# EuroESP32.net
KiCad netlist of a schematic drawn in EAGLE
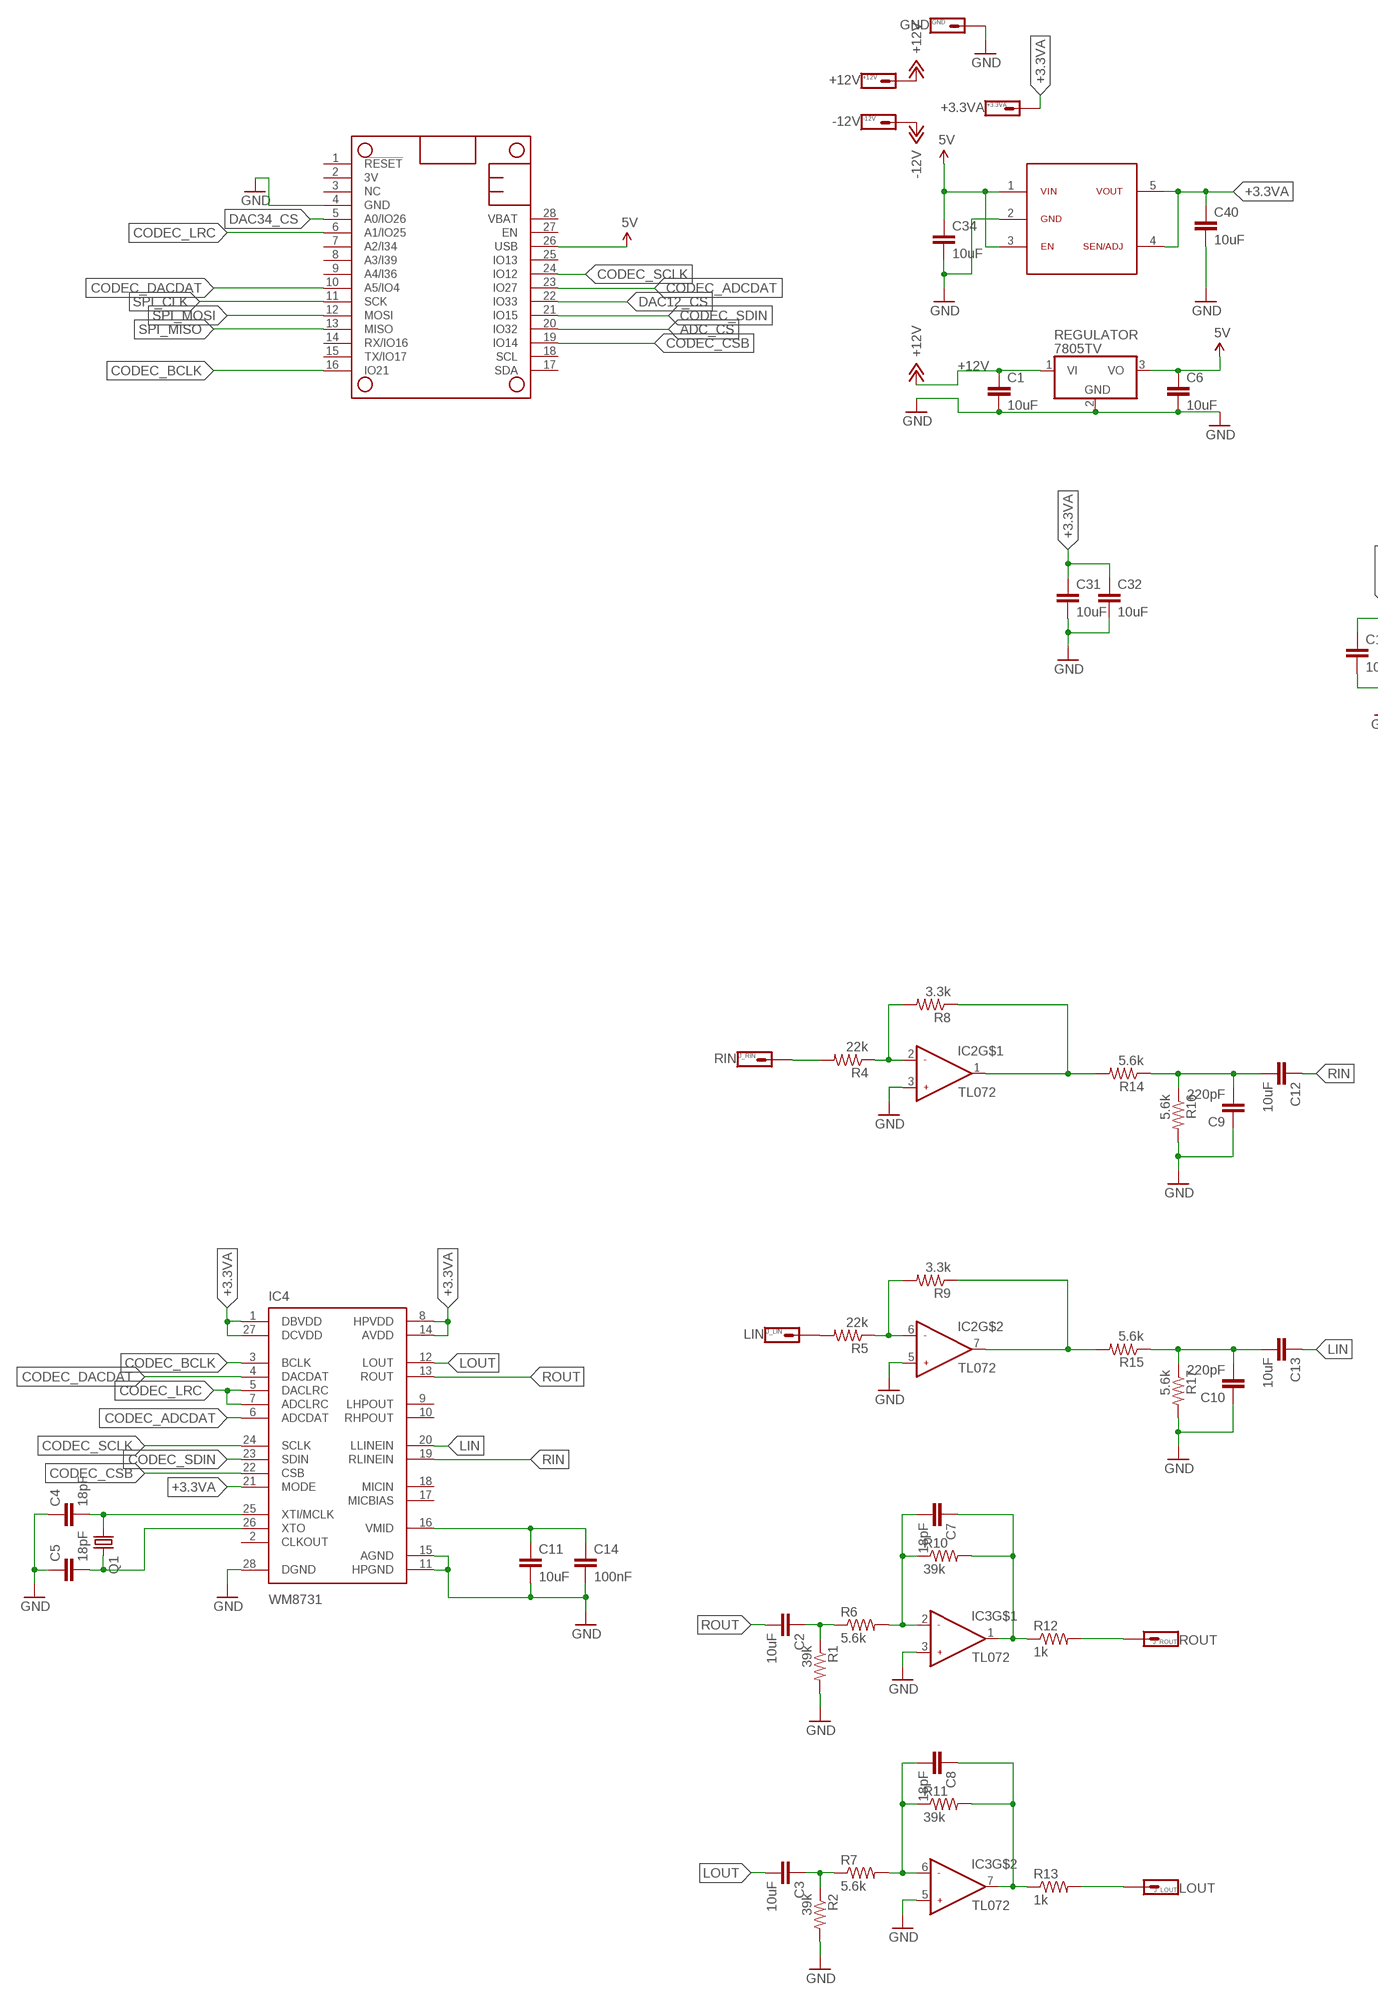
[diagram p0: schematic, sheet 1, part 1 of 2]
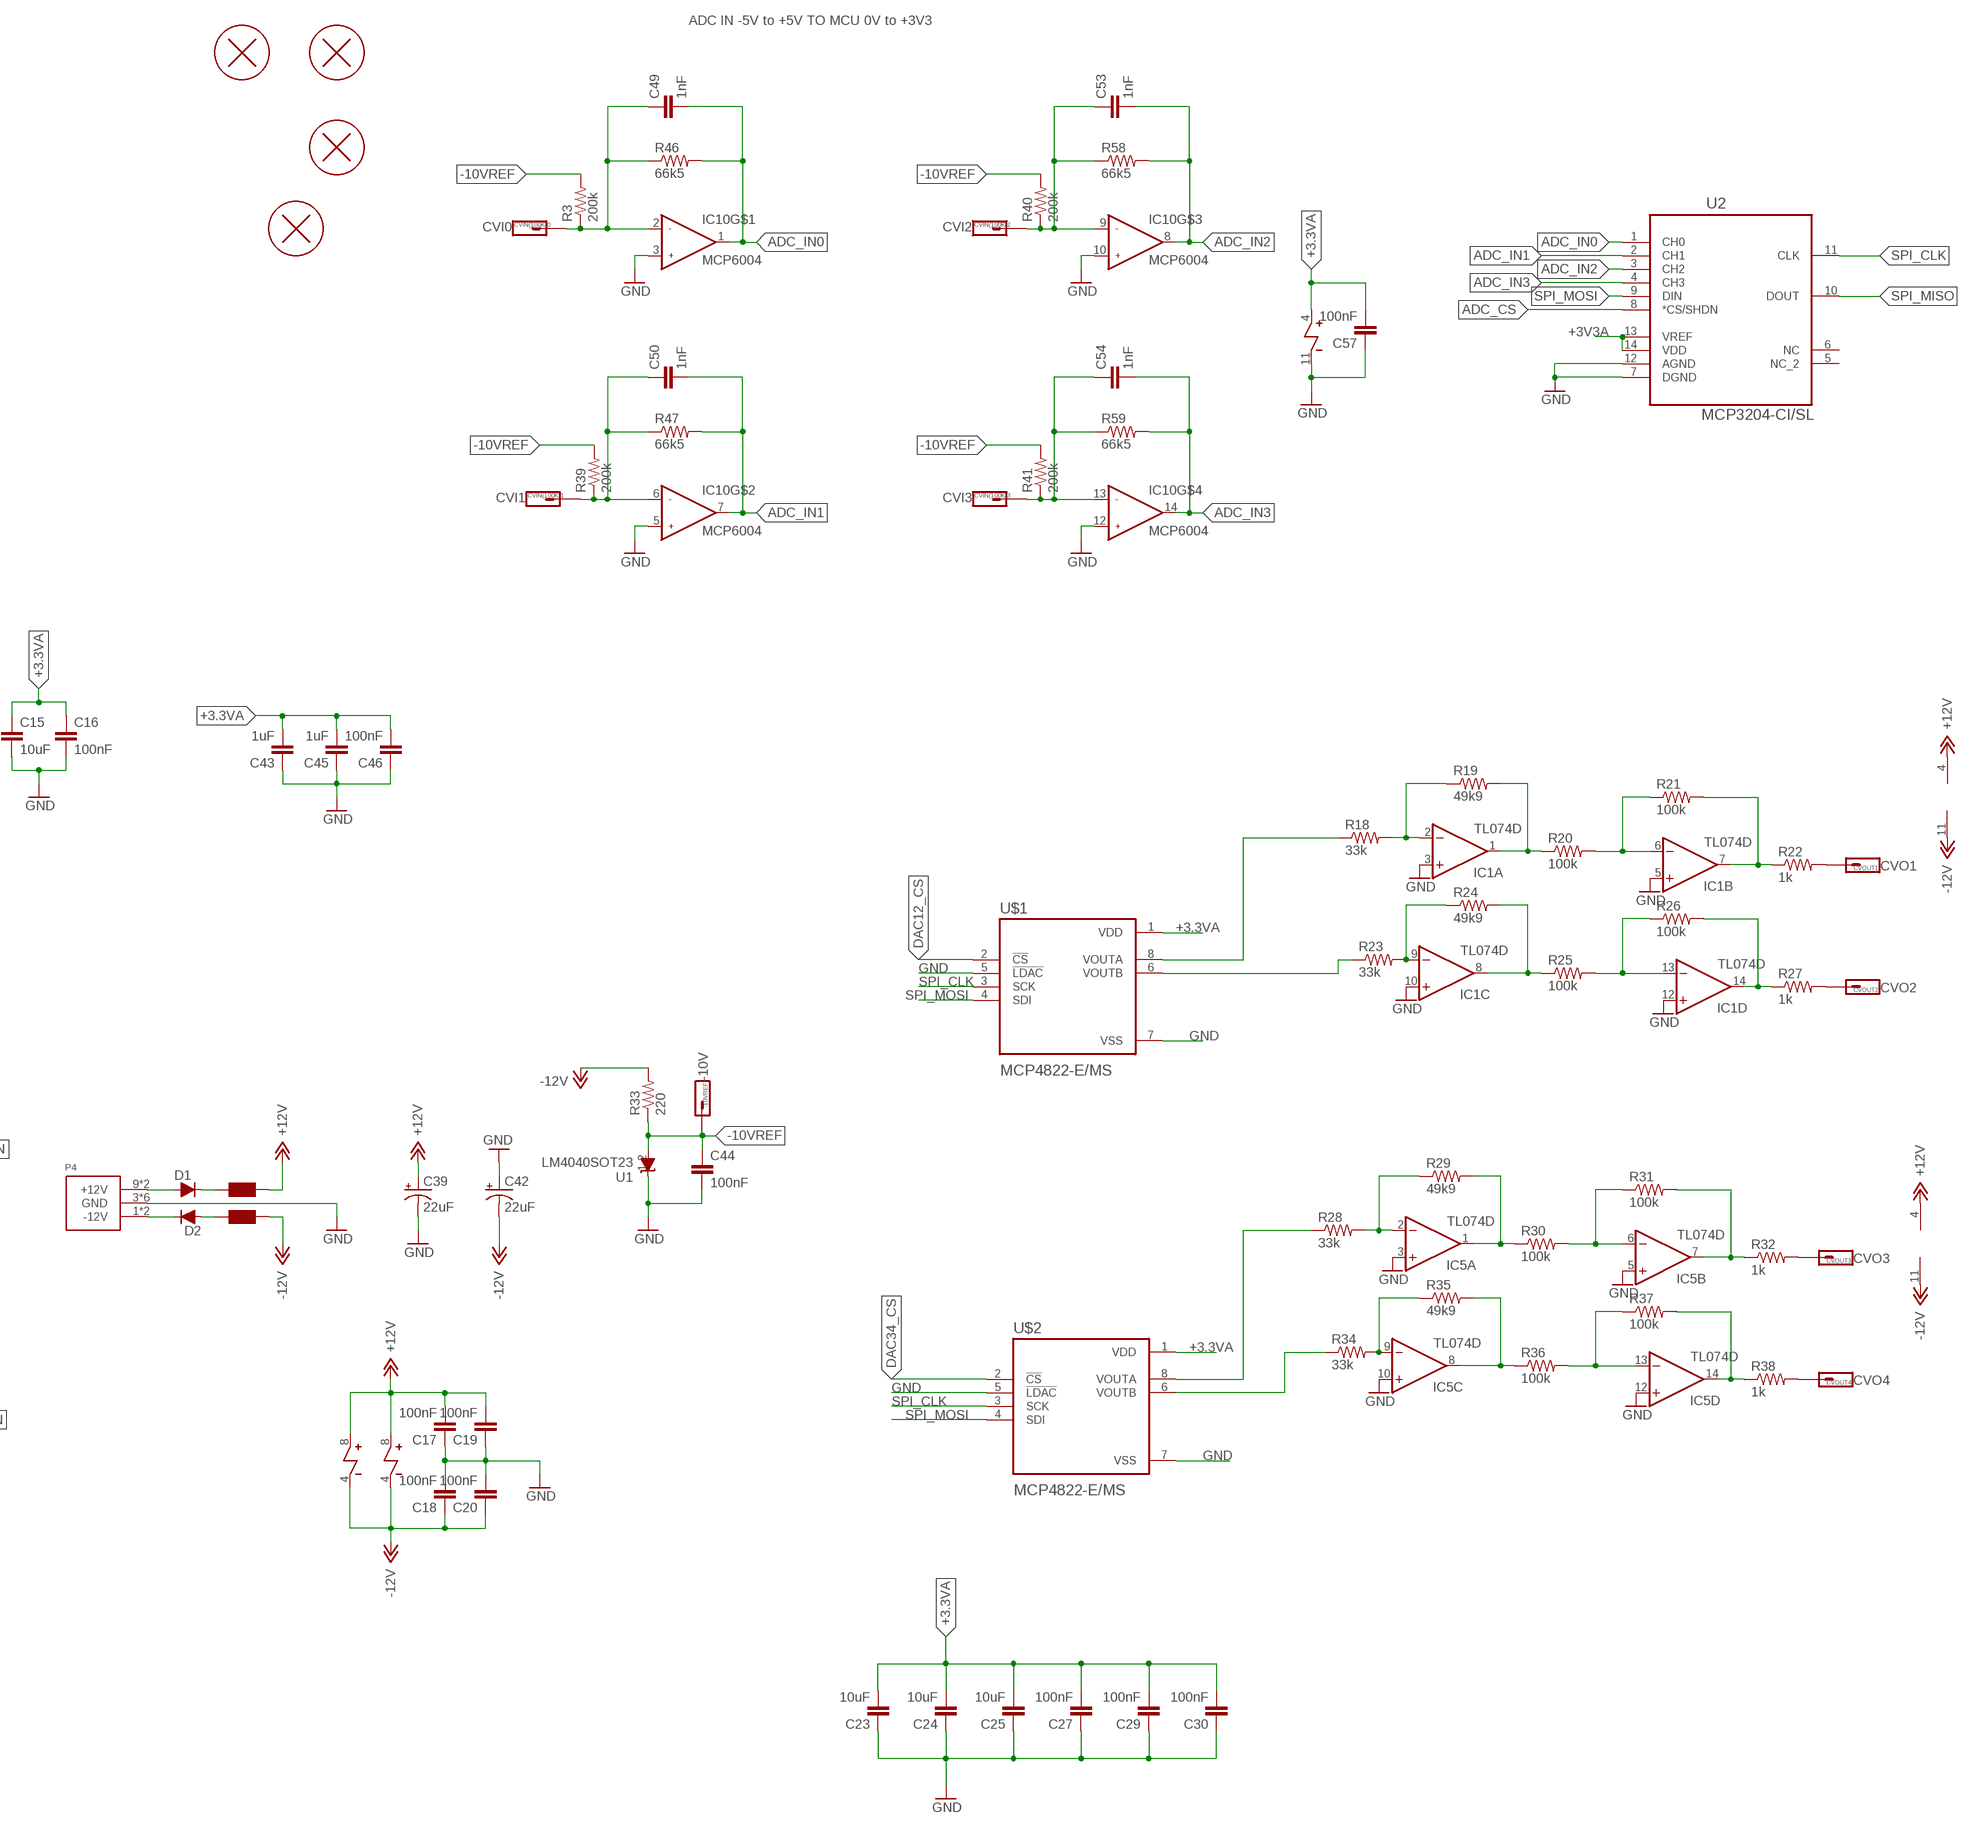
[diagram p1: schematic, sheet 1, part 2 of 2]

(export (version "E")
  (design (tool "Eeschema 10.0.6"))
  (components
    (comp (ref "+3.3VA")
      (value "+3.3VA")
      (footprint "eagle-import:1X01_SIDE_NAME")
      (libsource (lib "eagle-import") (part "HEADER-1X1"))
    )
    (comp (ref "+12V")
      (value "+12V")
      (footprint "eagle-import:1X01_SIDE_NAME")
      (libsource (lib "eagle-import") (part "HEADER-1X1"))
    )
    (comp (ref "-10VREF")
      (value "-10V")
      (footprint "eagle-import:1X01_SIDE_NAME")
      (libsource (lib "eagle-import") (part "HEADER-1X1"))
    )
    (comp (ref "-12V")
      (value "-12V")
      (footprint "eagle-import:1X01_SIDE_NAME")
      (libsource (lib "eagle-import") (part "HEADER-1X1"))
    )
    (comp (ref "C1")
      (value "10uF")
      (footprint "eagle-import:C2.5-2")
      (libsource (lib "eagle-import") (part "C2.5/2"))
    )
    (comp (ref "C2")
      (value "10uF")
      (footprint "eagle-import:R0805")
      (libsource (lib "eagle-import") (part "CAPACITOR0805"))
    )
    (comp (ref "C3")
      (value "10uF")
      (footprint "eagle-import:R0805")
      (libsource (lib "eagle-import") (part "CAPACITOR0805"))
    )
    (comp (ref "C4")
      (value "18pF")
      (footprint "eagle-import:RESISTOR_0603")
      (libsource (lib "eagle-import") (part "CAPACITOR"))
    )
    (comp (ref "C5")
      (value "18pF")
      (footprint "eagle-import:RESISTOR_0603")
      (libsource (lib "eagle-import") (part "CAPACITOR"))
    )
    (comp (ref "C6")
      (value "10uF")
      (footprint "eagle-import:C2.5-2")
      (libsource (lib "eagle-import") (part "C2.5/2"))
    )
    (comp (ref "C7")
      (value "18pF")
      (footprint "eagle-import:RESISTOR_0603")
      (libsource (lib "eagle-import") (part "CAPACITOR"))
    )
    (comp (ref "C8")
      (value "18pF")
      (footprint "eagle-import:RESISTOR_0603")
      (libsource (lib "eagle-import") (part "CAPACITOR"))
    )
    (comp (ref "C9")
      (value "220pF")
      (footprint "eagle-import:RESISTOR_0603")
      (libsource (lib "eagle-import") (part "CAPACITOR"))
    )
    (comp (ref "C10")
      (value "220pF")
      (footprint "eagle-import:RESISTOR_0603")
      (libsource (lib "eagle-import") (part "CAPACITOR"))
    )
    (comp (ref "C11")
      (value "10uF")
      (footprint "eagle-import:R0805")
      (libsource (lib "eagle-import") (part "CAPACITOR0805"))
    )
    (comp (ref "C12")
      (value "10uF")
      (footprint "eagle-import:R0805")
      (libsource (lib "eagle-import") (part "CAPACITOR0805"))
    )
    (comp (ref "C13")
      (value "10uF")
      (footprint "eagle-import:R0805")
      (libsource (lib "eagle-import") (part "CAPACITOR0805"))
    )
    (comp (ref "C14")
      (value "100nF")
      (footprint "eagle-import:RESISTOR_0603")
      (libsource (lib "eagle-import") (part "CAPACITOR"))
    )
    (comp (ref "C15")
      (value "10uF")
      (footprint "eagle-import:R0805")
      (libsource (lib "eagle-import") (part "CAPACITOR0805"))
    )
    (comp (ref "C16")
      (value "100nF")
      (footprint "eagle-import:RESISTOR_0603")
      (libsource (lib "eagle-import") (part "CAPACITOR"))
    )
    (comp (ref "C17")
      (value "100nF")
      (footprint "eagle-import:RESISTOR_0603")
      (libsource (lib "eagle-import") (part "CAPACITOR"))
    )
    (comp (ref "C18")
      (value "100nF")
      (footprint "eagle-import:RESISTOR_0603")
      (libsource (lib "eagle-import") (part "CAPACITOR"))
    )
    (comp (ref "C19")
      (value "100nF")
      (footprint "eagle-import:RESISTOR_0603")
      (libsource (lib "eagle-import") (part "CAPACITOR"))
    )
    (comp (ref "C20")
      (value "100nF")
      (footprint "eagle-import:RESISTOR_0603")
      (libsource (lib "eagle-import") (part "CAPACITOR"))
    )
    (comp (ref "C23")
      (value "10uF")
      (footprint "eagle-import:R0805")
      (libsource (lib "eagle-import") (part "CAPACITOR0805"))
    )
    (comp (ref "C24")
      (value "10uF")
      (footprint "eagle-import:R0805")
      (libsource (lib "eagle-import") (part "CAPACITOR0805"))
    )
    (comp (ref "C25")
      (value "10uF")
      (footprint "eagle-import:R0805")
      (libsource (lib "eagle-import") (part "CAPACITOR0805"))
    )
    (comp (ref "C27")
      (value "100nF")
      (footprint "eagle-import:RESISTOR_0603")
      (libsource (lib "eagle-import") (part "CAPACITOR"))
    )
    (comp (ref "C29")
      (value "100nF")
      (footprint "eagle-import:RESISTOR_0603")
      (libsource (lib "eagle-import") (part "CAPACITOR"))
    )
    (comp (ref "C30")
      (value "100nF")
      (footprint "eagle-import:RESISTOR_0603")
      (libsource (lib "eagle-import") (part "CAPACITOR"))
    )
    (comp (ref "C31")
      (value "10uF")
      (footprint "eagle-import:R0805")
      (libsource (lib "eagle-import") (part "CAPACITOR0805"))
    )
    (comp (ref "C32")
      (value "10uF")
      (footprint "eagle-import:R0805")
      (libsource (lib "eagle-import") (part "CAPACITOR0805"))
    )
    (comp (ref "C34")
      (value "10uF")
      (footprint "eagle-import:R1210")
      (libsource (lib "eagle-import") (part "CAPACITOR1210"))
    )
    (comp (ref "C39")
      (value "22uF")
      (footprint "eagle-import:1206_POL")
      (libsource (lib "eagle-import") (part "CAP_POL1206_TANT"))
    )
    (comp (ref "C40")
      (value "10uF")
      (footprint "eagle-import:R0805")
      (libsource (lib "eagle-import") (part "CAPACITOR0805"))
    )
    (comp (ref "C42")
      (value "22uF")
      (footprint "eagle-import:1206_POL")
      (libsource (lib "eagle-import") (part "CAP_POL1206_TANT"))
    )
    (comp (ref "C43")
      (value "1uF")
      (footprint "eagle-import:RESISTOR_0603")
      (libsource (lib "eagle-import") (part "CAPACITOR"))
    )
    (comp (ref "C44")
      (value "100nF")
      (footprint "eagle-import:RESISTOR_0603")
      (libsource (lib "eagle-import") (part "CAPACITOR"))
    )
    (comp (ref "C45")
      (value "1uF")
      (footprint "eagle-import:RESISTOR_0603")
      (libsource (lib "eagle-import") (part "CAPACITOR"))
    )
    (comp (ref "C46")
      (value "100nF")
      (footprint "eagle-import:RESISTOR_0603")
      (libsource (lib "eagle-import") (part "CAPACITOR"))
    )
    (comp (ref "C49")
      (value "1nF")
      (footprint "eagle-import:RESISTOR_0603")
      (libsource (lib "eagle-import") (part "CAPACITOR"))
    )
    (comp (ref "C50")
      (value "1nF")
      (footprint "eagle-import:RESISTOR_0603")
      (libsource (lib "eagle-import") (part "CAPACITOR"))
    )
    (comp (ref "C53")
      (value "1nF")
      (footprint "eagle-import:RESISTOR_0603")
      (libsource (lib "eagle-import") (part "CAPACITOR"))
    )
    (comp (ref "C54")
      (value "1nF")
      (footprint "eagle-import:RESISTOR_0603")
      (libsource (lib "eagle-import") (part "CAPACITOR"))
    )
    (comp (ref "C57")
      (value "100nF")
      (footprint "eagle-import:RESISTOR_0603")
      (libsource (lib "eagle-import") (part "CAPACITOR"))
    )
    (comp (ref "CVIN(100K)0")
      (value "CVI0")
      (footprint "eagle-import:1X01_SIDE_NAME")
      (libsource (lib "eagle-import") (part "HEADER-1X1"))
    )
    (comp (ref "CVIN(100K)1")
      (value "CVI1")
      (footprint "eagle-import:1X01_SIDE_NAME")
      (libsource (lib "eagle-import") (part "HEADER-1X1"))
    )
    (comp (ref "CVIN(100K)2")
      (value "CVI2")
      (footprint "eagle-import:1X01_SIDE_NAME")
      (libsource (lib "eagle-import") (part "HEADER-1X1"))
    )
    (comp (ref "CVIN(100K)3")
      (value "CVI3")
      (footprint "eagle-import:1X01_SIDE_NAME")
      (libsource (lib "eagle-import") (part "HEADER-1X1"))
    )
    (comp (ref "CVOUT1")
      (value "CVO1")
      (footprint "eagle-import:1X01_SIDE_NAME")
      (libsource (lib "eagle-import") (part "HEADER-1X1"))
    )
    (comp (ref "CVOUT2")
      (value "CVO2")
      (footprint "eagle-import:1X01_SIDE_NAME")
      (libsource (lib "eagle-import") (part "HEADER-1X1"))
    )
    (comp (ref "CVOUT3")
      (value "CVO3")
      (footprint "eagle-import:1X01_SIDE_NAME")
      (libsource (lib "eagle-import") (part "HEADER-1X1"))
    )
    (comp (ref "CVOUT4")
      (value "CVO4")
      (footprint "eagle-import:1X01_SIDE_NAME")
      (libsource (lib "eagle-import") (part "HEADER-1X1"))
    )
    (comp (ref "D1")
      (value "DIODE")
      (footprint "eagle-import:SOD123")
      (libsource (lib "eagle-import") (part "DIODE"))
    )
    (comp (ref "D2")
      (value "DIODE")
      (footprint "eagle-import:SOD123")
      (libsource (lib "eagle-import") (part "DIODE"))
    )
    (comp (ref "F1")
      (value "FERRITE-BEAD0805")
      (footprint "eagle-import:R0805")
      (libsource (lib "eagle-import") (part "FERRITE-BEAD0805"))
    )
    (comp (ref "F2")
      (value "FERRITE-BEAD0805")
      (footprint "eagle-import:R0805")
      (libsource (lib "eagle-import") (part "FERRITE-BEAD0805"))
    )
    (comp (ref "GND")
      (value "GND")
      (footprint "eagle-import:1X01_SIDE_NAME")
      (libsource (lib "eagle-import") (part "HEADER-1X1"))
    )
    (comp (ref "H1")
      (value "PCB_SCREW")
      (footprint "eagle-import:PCB_SCREW")
      (libsource (lib "eagle-import") (part "PCB_SCREW"))
    )
    (comp (ref "H3")
      (value "PCB_SCREW")
      (footprint "eagle-import:PCB_SCREW")
      (libsource (lib "eagle-import") (part "PCB_SCREW"))
    )
    (comp (ref "H4")
      (value "PCB_SCREW")
      (footprint "eagle-import:PCB_SCREW")
      (libsource (lib "eagle-import") (part "PCB_SCREW"))
    )
    (comp (ref "H5")
      (value "PCB_SCREW")
      (footprint "eagle-import:PCB_SCREW")
      (libsource (lib "eagle-import") (part "PCB_SCREW"))
    )
    (comp (ref "IC1")
      (value "TL074D")
      (footprint "eagle-import:SO14")
      (libsource (lib "eagle-import") (part "TL074D"))
    )
    (comp (ref "IC2")
      (value "TL072")
      (footprint "eagle-import:SOIC8")
      (libsource (lib "eagle-import") (part "OPAMP_DUAL"))
    )
    (comp (ref "IC3")
      (value "TL072")
      (footprint "eagle-import:SOIC8")
      (libsource (lib "eagle-import") (part "OPAMP_DUAL"))
    )
    (comp (ref "IC4")
      (value "WM8731")
      (footprint "eagle-import:SSOP28")
      (libsource (lib "eagle-import") (part "WM8731"))
    )
    (comp (ref "IC5")
      (value "TL074D")
      (footprint "eagle-import:SO14")
      (libsource (lib "eagle-import") (part "TL074D"))
    )
    (comp (ref "IC7")
      (value "ADP7118")
      (footprint "eagle-import:SOT23-5L")
      (libsource (lib "eagle-import") (part "ADP7118"))
    )
    (comp (ref "IC10")
      (value "MCP6004")
      (footprint "eagle-import:TSSOP14")
      (libsource (lib "eagle-import") (part "OPAMP_QUADPWR"))
    )
    (comp (ref "J_LIN")
      (value "LIN")
      (footprint "eagle-import:1X01_SIDE_NAME")
      (libsource (lib "eagle-import") (part "HEADER-1X1"))
    )
    (comp (ref "J_LOUT")
      (value "LOUT")
      (footprint "eagle-import:1X01_SIDE_NAME")
      (libsource (lib "eagle-import") (part "HEADER-1X1"))
    )
    (comp (ref "J_RIN")
      (value "RIN")
      (footprint "eagle-import:1X01_SIDE_NAME")
      (libsource (lib "eagle-import") (part "HEADER-1X1"))
    )
    (comp (ref "J_ROUT")
      (value "ROUT")
      (footprint "eagle-import:1X01_SIDE_NAME")
      (libsource (lib "eagle-import") (part "HEADER-1X1"))
    )
    (comp (ref "MS2")
      (value "FEATHER_HUZZAH32NO_DRILL")
      (footprint "eagle-import:FEATHERWING_NODRILL")
      (libsource (lib "eagle-import") (part "FEATHER_HUZZAH32NO_DRILL"))
    )
    (comp (ref "P4")
      (value "POWER_SIMPLE10")
      (footprint "eagle-import:POWER_10")
      (libsource (lib "eagle-import") (part "POWER_SIMPLE10"))
    )
    (comp (ref "Q1")
      (value "CRYSTAL")
      (footprint "eagle-import:HC49UP")
      (libsource (lib "eagle-import") (part "CRYSTAL"))
    )
    (comp (ref "R1")
      (value "39k")
      (footprint "eagle-import:RESISTOR_0603")
      (libsource (lib "eagle-import") (part "RESISTOR"))
    )
    (comp (ref "R2")
      (value "39k")
      (footprint "eagle-import:RESISTOR_0603")
      (libsource (lib "eagle-import") (part "RESISTOR"))
    )
    (comp (ref "R3")
      (value "200k")
      (footprint "eagle-import:RESISTOR_0603")
      (libsource (lib "eagle-import") (part "RESISTOR"))
    )
    (comp (ref "R4")
      (value "22k")
      (footprint "eagle-import:RESISTOR_0603")
      (libsource (lib "eagle-import") (part "RESISTOR"))
    )
    (comp (ref "R5")
      (value "22k")
      (footprint "eagle-import:RESISTOR_0603")
      (libsource (lib "eagle-import") (part "RESISTOR"))
    )
    (comp (ref "R6")
      (value "5.6k")
      (footprint "eagle-import:RESISTOR_0603")
      (libsource (lib "eagle-import") (part "RESISTOR"))
    )
    (comp (ref "R7")
      (value "5.6k")
      (footprint "eagle-import:RESISTOR_0603")
      (libsource (lib "eagle-import") (part "RESISTOR"))
    )
    (comp (ref "R8")
      (value "3.3k")
      (footprint "eagle-import:RESISTOR_0603")
      (libsource (lib "eagle-import") (part "RESISTOR"))
    )
    (comp (ref "R9")
      (value "3.3k")
      (footprint "eagle-import:RESISTOR_0603")
      (libsource (lib "eagle-import") (part "RESISTOR"))
    )
    (comp (ref "R10")
      (value "39k")
      (footprint "eagle-import:RESISTOR_0603")
      (libsource (lib "eagle-import") (part "RESISTOR"))
    )
    (comp (ref "R11")
      (value "39k")
      (footprint "eagle-import:RESISTOR_0603")
      (libsource (lib "eagle-import") (part "RESISTOR"))
    )
    (comp (ref "R12")
      (value "1k")
      (footprint "eagle-import:RESISTOR_0603")
      (libsource (lib "eagle-import") (part "RESISTOR"))
    )
    (comp (ref "R13")
      (value "1k")
      (footprint "eagle-import:RESISTOR_0603")
      (libsource (lib "eagle-import") (part "RESISTOR"))
    )
    (comp (ref "R14")
      (value "5.6k")
      (footprint "eagle-import:RESISTOR_0603")
      (libsource (lib "eagle-import") (part "RESISTOR"))
    )
    (comp (ref "R15")
      (value "5.6k")
      (footprint "eagle-import:RESISTOR_0603")
      (libsource (lib "eagle-import") (part "RESISTOR"))
    )
    (comp (ref "R16")
      (value "5.6k")
      (footprint "eagle-import:RESISTOR_0603")
      (libsource (lib "eagle-import") (part "RESISTOR"))
    )
    (comp (ref "R17")
      (value "5.6k")
      (footprint "eagle-import:RESISTOR_0603")
      (libsource (lib "eagle-import") (part "RESISTOR"))
    )
    (comp (ref "R18")
      (value "33k")
      (footprint "eagle-import:RESISTOR_0603")
      (libsource (lib "eagle-import") (part "RESISTOR"))
    )
    (comp (ref "R19")
      (value "49k9")
      (footprint "eagle-import:RESISTOR_0603")
      (libsource (lib "eagle-import") (part "RESISTOR"))
    )
    (comp (ref "R20")
      (value "100k")
      (footprint "eagle-import:RESISTOR_0603")
      (libsource (lib "eagle-import") (part "RESISTOR"))
    )
    (comp (ref "R21")
      (value "100k")
      (footprint "eagle-import:RESISTOR_0603")
      (libsource (lib "eagle-import") (part "RESISTOR"))
    )
    (comp (ref "R22")
      (value "1k")
      (footprint "eagle-import:RESISTOR_0603")
      (libsource (lib "eagle-import") (part "RESISTOR"))
    )
    (comp (ref "R23")
      (value "33k")
      (footprint "eagle-import:RESISTOR_0603")
      (libsource (lib "eagle-import") (part "RESISTOR"))
    )
    (comp (ref "R24")
      (value "49k9")
      (footprint "eagle-import:RESISTOR_0603")
      (libsource (lib "eagle-import") (part "RESISTOR"))
    )
    (comp (ref "R25")
      (value "100k")
      (footprint "eagle-import:RESISTOR_0603")
      (libsource (lib "eagle-import") (part "RESISTOR"))
    )
    (comp (ref "R26")
      (value "100k")
      (footprint "eagle-import:RESISTOR_0603")
      (libsource (lib "eagle-import") (part "RESISTOR"))
    )
    (comp (ref "R27")
      (value "1k")
      (footprint "eagle-import:RESISTOR_0603")
      (libsource (lib "eagle-import") (part "RESISTOR"))
    )
    (comp (ref "R28")
      (value "33k")
      (footprint "eagle-import:RESISTOR_0603")
      (libsource (lib "eagle-import") (part "RESISTOR"))
    )
    (comp (ref "R29")
      (value "49k9")
      (footprint "eagle-import:RESISTOR_0603")
      (libsource (lib "eagle-import") (part "RESISTOR"))
    )
    (comp (ref "R30")
      (value "100k")
      (footprint "eagle-import:RESISTOR_0603")
      (libsource (lib "eagle-import") (part "RESISTOR"))
    )
    (comp (ref "R31")
      (value "100k")
      (footprint "eagle-import:RESISTOR_0603")
      (libsource (lib "eagle-import") (part "RESISTOR"))
    )
    (comp (ref "R32")
      (value "1k")
      (footprint "eagle-import:RESISTOR_0603")
      (libsource (lib "eagle-import") (part "RESISTOR"))
    )
    (comp (ref "R33")
      (value "220")
      (footprint "eagle-import:RESISTOR_0603")
      (libsource (lib "eagle-import") (part "RESISTOR"))
    )
    (comp (ref "R34")
      (value "33k")
      (footprint "eagle-import:RESISTOR_0603")
      (libsource (lib "eagle-import") (part "RESISTOR"))
    )
    (comp (ref "R35")
      (value "49k9")
      (footprint "eagle-import:RESISTOR_0603")
      (libsource (lib "eagle-import") (part "RESISTOR"))
    )
    (comp (ref "R36")
      (value "100k")
      (footprint "eagle-import:RESISTOR_0603")
      (libsource (lib "eagle-import") (part "RESISTOR"))
    )
    (comp (ref "R37")
      (value "100k")
      (footprint "eagle-import:RESISTOR_0603")
      (libsource (lib "eagle-import") (part "RESISTOR"))
    )
    (comp (ref "R38")
      (value "1k")
      (footprint "eagle-import:RESISTOR_0603")
      (libsource (lib "eagle-import") (part "RESISTOR"))
    )
    (comp (ref "R39")
      (value "200k")
      (footprint "eagle-import:RESISTOR_0603")
      (libsource (lib "eagle-import") (part "RESISTOR"))
    )
    (comp (ref "R40")
      (value "200k")
      (footprint "eagle-import:RESISTOR_0603")
      (libsource (lib "eagle-import") (part "RESISTOR"))
    )
    (comp (ref "R41")
      (value "200k")
      (footprint "eagle-import:RESISTOR_0603")
      (libsource (lib "eagle-import") (part "RESISTOR"))
    )
    (comp (ref "R46")
      (value "66k5")
      (footprint "eagle-import:RESISTOR_0603")
      (libsource (lib "eagle-import") (part "RESISTOR"))
    )
    (comp (ref "R47")
      (value "66k5")
      (footprint "eagle-import:RESISTOR_0603")
      (libsource (lib "eagle-import") (part "RESISTOR"))
    )
    (comp (ref "R58")
      (value "66k5")
      (footprint "eagle-import:RESISTOR_0603")
      (libsource (lib "eagle-import") (part "RESISTOR"))
    )
    (comp (ref "R59")
      (value "66k5")
      (footprint "eagle-import:RESISTOR_0603")
      (libsource (lib "eagle-import") (part "RESISTOR"))
    )
    (comp (ref "REGULATOR")
      (value "7805TV")
      (footprint "eagle-import:TO220V")
      (libsource (lib "eagle-import") (part "78TV05"))
    )
    (comp (ref "U$1")
      (value "MCP4822-E/MS")
      (footprint "eagle-import:SOP65P490X110-8N")
      (fields (field (name "MF") "Microchip Technology"))
      (libsource (lib "eagle-import") (part "MCP4822-E/MS"))
    )
    (comp (ref "U$2")
      (value "MCP4822-E/MS")
      (footprint "eagle-import:SOP65P490X110-8N")
      (fields (field (name "MF") "Microchip Technology"))
      (libsource (lib "eagle-import") (part "MCP4822-E/MS"))
    )
    (comp (ref "U1")
      (value "LM4040SOT23")
      (footprint "eagle-import:SOT23")
      (libsource (lib "eagle-import") (part "LM4040SOT23"))
    )
    (comp (ref "U2")
      (value "MCP3204-CI/SL")
      (footprint "eagle-import:SOIC127P600X175-14N")
      (libsource (lib "eagle-import") (part "MCP3204-CI/SL"))
    )
  )
  (nets
    (net (code "1") (name "+3.3VA") (class "Default")
      (node (ref "+3.3VA") (pin "1") (pinfunction "1_1") (pintype "passive"))
      (node (ref "C15") (pin "1") (pinfunction "1_1") (pintype "passive"))
      (node (ref "C16") (pin "1") (pinfunction "1_1") (pintype "passive"))
      (node (ref "C23") (pin "2") (pinfunction "2_2") (pintype "passive"))
      (node (ref "C24") (pin "2") (pinfunction "2_2") (pintype "passive"))
      (node (ref "C25") (pin "2") (pinfunction "2_2") (pintype "passive"))
      (node (ref "C27") (pin "2") (pinfunction "2_2") (pintype "passive"))
      (node (ref "C29") (pin "2") (pinfunction "2_2") (pintype "passive"))
      (node (ref "C30") (pin "2") (pinfunction "2_2") (pintype "passive"))
      (node (ref "C31") (pin "1") (pinfunction "1_1") (pintype "passive"))
      (node (ref "C32") (pin "1") (pinfunction "1_1") (pintype "passive"))
      (node (ref "C40") (pin "1") (pinfunction "1_1") (pintype "passive"))
      (node (ref "C43") (pin "2") (pinfunction "2_2") (pintype "passive"))
      (node (ref "C45") (pin "2") (pinfunction "2_2") (pintype "passive"))
      (node (ref "C46") (pin "2") (pinfunction "2_2") (pintype "passive"))
      (node (ref "C57") (pin "2") (pinfunction "2_2") (pintype "passive"))
      (node (ref "IC10") (pin "4") (pinfunction "P$1_4") (pintype "bidirectional"))
      (node (ref "IC4") (pin "1") (pinfunction "DBVDD_1") (pintype "bidirectional"))
      (node (ref "IC4") (pin "14") (pinfunction "AVDD_14") (pintype "bidirectional"))
      (node (ref "IC4") (pin "21") (pinfunction "MODE_21") (pintype "bidirectional"))
      (node (ref "IC4") (pin "27") (pinfunction "DCVDD_27") (pintype "bidirectional"))
      (node (ref "IC4") (pin "8") (pinfunction "HPVDD_8") (pintype "bidirectional"))
      (node (ref "IC7") (pin "4") (pinfunction "P$4_4") (pintype "bidirectional"))
      (node (ref "IC7") (pin "5") (pinfunction "P$5_5") (pintype "bidirectional"))
      (node (ref "U$1") (pin "1") (pinfunction "VDD_1") (pintype "power_in"))
      (node (ref "U$2") (pin "1") (pinfunction "VDD_1") (pintype "power_in"))
    )
    (net (code "2") (name "+12V") (class "Default")
      (node (ref "+12V") (pin "1") (pinfunction "1_1") (pintype "passive"))
      (node (ref "C1") (pin "1") (pinfunction "1_1") (pintype "passive"))
      (node (ref "C17") (pin "2") (pinfunction "2_2") (pintype "passive"))
      (node (ref "C19") (pin "2") (pinfunction "2_2") (pintype "passive"))
      (node (ref "C39") (pin "2") (pinfunction "+_2") (pintype "passive"))
      (node (ref "F1") (pin "1") (pinfunction "P$1_1") (pintype "bidirectional"))
      (node (ref "IC1") (pin "4") (pinfunction "V+_4") (pintype "power_in"))
      (node (ref "IC2") (pin "8") (pinfunction "P$1_8") (pintype "bidirectional"))
      (node (ref "IC3") (pin "8") (pinfunction "P$1_8") (pintype "bidirectional"))
      (node (ref "IC5") (pin "4") (pinfunction "V+_4") (pintype "power_in"))
      (node (ref "REGULATOR") (pin "1") (pinfunction "VI_1") (pintype "input"))
    )
    (net (code "3") (name "-10VREF") (class "Default")
      (node (ref "-10VREF") (pin "1") (pinfunction "1_1") (pintype "passive"))
      (node (ref "C44") (pin "1") (pinfunction "1_1") (pintype "passive"))
      (node (ref "R3") (pin "2") (pinfunction "2_2") (pintype "passive"))
      (node (ref "R33") (pin "1") (pinfunction "1_1") (pintype "passive"))
      (node (ref "R39") (pin "2") (pinfunction "2_2") (pintype "passive"))
      (node (ref "R40") (pin "2") (pinfunction "2_2") (pintype "passive"))
      (node (ref "R41") (pin "2") (pinfunction "2_2") (pintype "passive"))
      (node (ref "U1") (pin "2") (pinfunction "A_2") (pintype "passive"))
    )
    (net (code "4") (name "-12V") (class "Default")
      (node (ref "-12V") (pin "1") (pinfunction "1_1") (pintype "passive"))
      (node (ref "C18") (pin "1") (pinfunction "1_1") (pintype "passive"))
      (node (ref "C20") (pin "1") (pinfunction "1_1") (pintype "passive"))
      (node (ref "C42") (pin "1") (pinfunction "-_1") (pintype "passive"))
      (node (ref "F2") (pin "1") (pinfunction "P$1_1") (pintype "bidirectional"))
      (node (ref "IC1") (pin "11") (pinfunction "V-_11") (pintype "power_in"))
      (node (ref "IC2") (pin "4") (pinfunction "P$2_4") (pintype "bidirectional"))
      (node (ref "IC3") (pin "4") (pinfunction "P$2_4") (pintype "bidirectional"))
      (node (ref "IC5") (pin "11") (pinfunction "V-_11") (pintype "power_in"))
      (node (ref "R33") (pin "2") (pinfunction "2_2") (pintype "passive"))
    )
    (net (code "5") (name "/+3V3A") (class "Default")
      (node (ref "U2") (pin "13") (pinfunction "VREF_13") (pintype "input"))
      (node (ref "U2") (pin "14") (pinfunction "VDD_14") (pintype "power_in"))
    )
    (net (code "6") (name "/3V") (class "Default")
      (node (ref "MS2") (pin "2") (pinfunction "3V_2") (pintype "power_in"))
    )
    (net (code "7") (name "/VBAT") (class "Default")
      (node (ref "MS2") (pin "28") (pinfunction "VBAT_28") (pintype "power_in"))
    )
    (net (code "8") (name "5V") (class "Default")
      (node (ref "C34") (pin "1") (pinfunction "1_1") (pintype "passive"))
      (node (ref "C6") (pin "1") (pinfunction "1_1") (pintype "passive"))
      (node (ref "IC7") (pin "1") (pinfunction "P$1_1") (pintype "bidirectional"))
      (node (ref "IC7") (pin "3") (pinfunction "P$3_3") (pintype "bidirectional"))
      (node (ref "MS2") (pin "26") (pinfunction "USB_26") (pintype "power_in"))
      (node (ref "REGULATOR") (pin "3") (pinfunction "VO_3") (pintype "passive"))
    )
    (net (code "9") (name "ADC_CS") (class "Default")
      (node (ref "MS2") (pin "20") (pinfunction "IO32_20") (pintype "bidirectional"))
      (node (ref "U2") (pin "8") (pinfunction "*CS/SHDN_8") (pintype "input"))
    )
    (net (code "10") (name "ADC_IN0") (class "Default")
      (node (ref "C49") (pin "2") (pinfunction "2_2") (pintype "passive"))
      (node (ref "IC10") (pin "1") (pinfunction "P$3_1") (pintype "bidirectional"))
      (node (ref "R46") (pin "2") (pinfunction "2_2") (pintype "passive"))
      (node (ref "U2") (pin "1") (pinfunction "CH0_1") (pintype "input"))
    )
    (net (code "11") (name "ADC_IN1") (class "Default")
      (node (ref "C50") (pin "2") (pinfunction "2_2") (pintype "passive"))
      (node (ref "IC10") (pin "7") (pinfunction "P$3_7") (pintype "bidirectional"))
      (node (ref "R47") (pin "2") (pinfunction "2_2") (pintype "passive"))
      (node (ref "U2") (pin "2") (pinfunction "CH1_2") (pintype "input"))
    )
    (net (code "12") (name "ADC_IN2") (class "Default")
      (node (ref "C53") (pin "2") (pinfunction "2_2") (pintype "passive"))
      (node (ref "IC10") (pin "8") (pinfunction "P$3_8") (pintype "bidirectional"))
      (node (ref "R58") (pin "2") (pinfunction "2_2") (pintype "passive"))
      (node (ref "U2") (pin "3") (pinfunction "CH2_3") (pintype "input"))
    )
    (net (code "13") (name "ADC_IN3") (class "Default")
      (node (ref "C54") (pin "2") (pinfunction "2_2") (pintype "passive"))
      (node (ref "IC10") (pin "14") (pinfunction "P$3_14") (pintype "bidirectional"))
      (node (ref "R59") (pin "2") (pinfunction "2_2") (pintype "passive"))
      (node (ref "U2") (pin "4") (pinfunction "CH3_4") (pintype "input"))
    )
    (net (code "14") (name "CODEC_ADCDAT") (class "Default")
      (node (ref "IC4") (pin "6") (pinfunction "ADCDAT_6") (pintype "bidirectional"))
      (node (ref "MS2") (pin "23") (pinfunction "IO27_23") (pintype "bidirectional"))
    )
    (net (code "15") (name "CODEC_BCLK") (class "Default")
      (node (ref "IC4") (pin "3") (pinfunction "BCLK_3") (pintype "bidirectional"))
      (node (ref "MS2") (pin "16") (pinfunction "IO21_16") (pintype "passive"))
    )
    (net (code "16") (name "CODEC_CSB") (class "Default")
      (node (ref "IC4") (pin "22") (pinfunction "CSB_22") (pintype "bidirectional"))
      (node (ref "MS2") (pin "19") (pinfunction "IO14_19") (pintype "bidirectional"))
    )
    (net (code "17") (name "CODEC_DACDAT") (class "Default")
      (node (ref "IC4") (pin "4") (pinfunction "DACDAT_4") (pintype "bidirectional"))
      (node (ref "MS2") (pin "10") (pinfunction "A5/IO4_10") (pintype "bidirectional"))
    )
    (net (code "18") (name "CODEC_LRC") (class "Default")
      (node (ref "IC4") (pin "5") (pinfunction "DACLRC_5") (pintype "bidirectional"))
      (node (ref "IC4") (pin "7") (pinfunction "ADCLRC_7") (pintype "bidirectional"))
      (node (ref "MS2") (pin "6") (pinfunction "A1/IO25_6") (pintype "bidirectional"))
    )
    (net (code "19") (name "CODEC_SCLK") (class "Default")
      (node (ref "IC4") (pin "24") (pinfunction "SCLK_24") (pintype "bidirectional"))
      (node (ref "MS2") (pin "24") (pinfunction "IO12_24") (pintype "bidirectional"))
    )
    (net (code "20") (name "CODEC_SDIN") (class "Default")
      (node (ref "IC4") (pin "23") (pinfunction "SDIN_23") (pintype "bidirectional"))
      (node (ref "MS2") (pin "21") (pinfunction "IO15_21") (pintype "bidirectional"))
    )
    (net (code "21") (name "DAC12_CS") (class "Default")
      (node (ref "MS2") (pin "22") (pinfunction "IO33_22") (pintype "bidirectional"))
      (node (ref "U$1") (pin "2") (pinfunction "~{CS}_2") (pintype "input"))
    )
    (net (code "22") (name "DAC34_CS") (class "Default")
      (node (ref "MS2") (pin "5") (pinfunction "A0/IO26_5") (pintype "bidirectional"))
      (node (ref "U$2") (pin "2") (pinfunction "~{CS}_2") (pintype "input"))
    )
    (net (code "23") (name "GND") (class "Default")
      (node (ref "C1") (pin "2") (pinfunction "2_2") (pintype "passive"))
      (node (ref "C10") (pin "1") (pinfunction "1_1") (pintype "passive"))
      (node (ref "C11") (pin "2") (pinfunction "2_2") (pintype "passive"))
      (node (ref "C14") (pin "2") (pinfunction "2_2") (pintype "passive"))
      (node (ref "C15") (pin "2") (pinfunction "2_2") (pintype "passive"))
      (node (ref "C16") (pin "2") (pinfunction "2_2") (pintype "passive"))
      (node (ref "C17") (pin "1") (pinfunction "1_1") (pintype "passive"))
      (node (ref "C18") (pin "2") (pinfunction "2_2") (pintype "passive"))
      (node (ref "C19") (pin "1") (pinfunction "1_1") (pintype "passive"))
      (node (ref "C20") (pin "2") (pinfunction "2_2") (pintype "passive"))
      (node (ref "C23") (pin "1") (pinfunction "1_1") (pintype "passive"))
      (node (ref "C24") (pin "1") (pinfunction "1_1") (pintype "passive"))
      (node (ref "C25") (pin "1") (pinfunction "1_1") (pintype "passive"))
      (node (ref "C27") (pin "1") (pinfunction "1_1") (pintype "passive"))
      (node (ref "C29") (pin "1") (pinfunction "1_1") (pintype "passive"))
      (node (ref "C30") (pin "1") (pinfunction "1_1") (pintype "passive"))
      (node (ref "C31") (pin "2") (pinfunction "2_2") (pintype "passive"))
      (node (ref "C32") (pin "2") (pinfunction "2_2") (pintype "passive"))
      (node (ref "C34") (pin "2") (pinfunction "2_2") (pintype "passive"))
      (node (ref "C39") (pin "1") (pinfunction "-_1") (pintype "passive"))
      (node (ref "C4") (pin "1") (pinfunction "1_1") (pintype "passive"))
      (node (ref "C40") (pin "2") (pinfunction "2_2") (pintype "passive"))
      (node (ref "C42") (pin "2") (pinfunction "+_2") (pintype "passive"))
      (node (ref "C43") (pin "1") (pinfunction "1_1") (pintype "passive"))
      (node (ref "C44") (pin "2") (pinfunction "2_2") (pintype "passive"))
      (node (ref "C45") (pin "1") (pinfunction "1_1") (pintype "passive"))
      (node (ref "C46") (pin "1") (pinfunction "1_1") (pintype "passive"))
      (node (ref "C5") (pin "1") (pinfunction "1_1") (pintype "passive"))
      (node (ref "C57") (pin "1") (pinfunction "1_1") (pintype "passive"))
      (node (ref "C6") (pin "2") (pinfunction "2_2") (pintype "passive"))
      (node (ref "C9") (pin "1") (pinfunction "1_1") (pintype "passive"))
      (node (ref "GND") (pin "1") (pinfunction "1_1") (pintype "passive"))
      (node (ref "IC1") (pin "10") (pinfunction "+IN_10") (pintype "input"))
      (node (ref "IC1") (pin "12") (pinfunction "+IN_12") (pintype "input"))
      (node (ref "IC1") (pin "3") (pinfunction "+IN_3") (pintype "input"))
      (node (ref "IC1") (pin "5") (pinfunction "+IN_5") (pintype "input"))
      (node (ref "IC10") (pin "10") (pinfunction "P$1_10") (pintype "bidirectional"))
      (node (ref "IC10") (pin "11") (pinfunction "P$2_11") (pintype "bidirectional"))
      (node (ref "IC10") (pin "12") (pinfunction "P$1_12") (pintype "bidirectional"))
      (node (ref "IC10") (pin "3") (pinfunction "P$1_3") (pintype "bidirectional"))
      (node (ref "IC10") (pin "5") (pinfunction "P$1_5") (pintype "bidirectional"))
      (node (ref "IC2") (pin "3") (pinfunction "P$1_3") (pintype "bidirectional"))
      (node (ref "IC2") (pin "5") (pinfunction "P$1_5") (pintype "bidirectional"))
      (node (ref "IC3") (pin "3") (pinfunction "P$1_3") (pintype "bidirectional"))
      (node (ref "IC3") (pin "5") (pinfunction "P$1_5") (pintype "bidirectional"))
      (node (ref "IC4") (pin "11") (pinfunction "HPGND_11") (pintype "bidirectional"))
      (node (ref "IC4") (pin "15") (pinfunction "AGND_15") (pintype "bidirectional"))
      (node (ref "IC4") (pin "28") (pinfunction "DGND_28") (pintype "bidirectional"))
      (node (ref "IC5") (pin "10") (pinfunction "+IN_10") (pintype "input"))
      (node (ref "IC5") (pin "12") (pinfunction "+IN_12") (pintype "input"))
      (node (ref "IC5") (pin "3") (pinfunction "+IN_3") (pintype "input"))
      (node (ref "IC5") (pin "5") (pinfunction "+IN_5") (pintype "input"))
      (node (ref "IC7") (pin "2") (pinfunction "P$2_2") (pintype "bidirectional"))
      (node (ref "MS2") (pin "4") (pinfunction "GND_4") (pintype "power_in"))
      (node (ref "P4") (pin "3") (pinfunction "GND_3") (pintype "bidirectional"))
      (node (ref "P4") (pin "4") (pinfunction "GND_4") (pintype "bidirectional"))
      (node (ref "P4") (pin "5") (pinfunction "GND_5") (pintype "bidirectional"))
      (node (ref "P4") (pin "6") (pinfunction "GND_6") (pintype "bidirectional"))
      (node (ref "P4") (pin "7") (pinfunction "GND_7") (pintype "bidirectional"))
      (node (ref "P4") (pin "8") (pinfunction "GND_8") (pintype "bidirectional"))
      (node (ref "R1") (pin "2") (pinfunction "2_2") (pintype "passive"))
      (node (ref "R16") (pin "2") (pinfunction "2_2") (pintype "passive"))
      (node (ref "R17") (pin "2") (pinfunction "2_2") (pintype "passive"))
      (node (ref "R2") (pin "2") (pinfunction "2_2") (pintype "passive"))
      (node (ref "REGULATOR") (pin "2") (pinfunction "GND_2") (pintype "passive"))
      (node (ref "U$1") (pin "5") (pinfunction "~{LDAC}_5") (pintype "input"))
      (node (ref "U$1") (pin "7") (pinfunction "VSS_7") (pintype "power_in"))
      (node (ref "U$2") (pin "5") (pinfunction "~{LDAC}_5") (pintype "input"))
      (node (ref "U$2") (pin "7") (pinfunction "VSS_7") (pintype "power_in"))
      (node (ref "U1") (pin "1") (pinfunction "C_1") (pintype "passive"))
      (node (ref "U2") (pin "12") (pinfunction "AGND_12") (pintype "passive"))
      (node (ref "U2") (pin "7") (pinfunction "DGND_7") (pintype "passive"))
    )
    (net (code "24") (name "LIN") (class "Default")
      (node (ref "C13") (pin "1") (pinfunction "1_1") (pintype "passive"))
      (node (ref "IC4") (pin "20") (pinfunction "LLINEIN_20") (pintype "bidirectional"))
    )
    (net (code "25") (name "LOUT") (class "Default")
      (node (ref "C3") (pin "2") (pinfunction "2_2") (pintype "passive"))
      (node (ref "IC4") (pin "12") (pinfunction "LOUT_12") (pintype "bidirectional"))
    )
    (net (code "26") (name "Net-(C2-Pad1)") (class "Default")
      (node (ref "C2") (pin "1") (pinfunction "1_1") (pintype "passive"))
      (node (ref "R1") (pin "1") (pinfunction "1_1") (pintype "passive"))
      (node (ref "R6") (pin "1") (pinfunction "1_1") (pintype "passive"))
    )
    (net (code "27") (name "Net-(C3-Pad1)") (class "Default")
      (node (ref "C3") (pin "1") (pinfunction "1_1") (pintype "passive"))
      (node (ref "R2") (pin "1") (pinfunction "1_1") (pintype "passive"))
      (node (ref "R7") (pin "1") (pinfunction "1_1") (pintype "passive"))
    )
    (net (code "28") (name "Net-(C10-Pad2)") (class "Default")
      (node (ref "C10") (pin "2") (pinfunction "2_2") (pintype "passive"))
      (node (ref "C13") (pin "2") (pinfunction "2_2") (pintype "passive"))
      (node (ref "R15") (pin "1") (pinfunction "1_1") (pintype "passive"))
      (node (ref "R17") (pin "1") (pinfunction "1_1") (pintype "passive"))
    )
    (net (code "29") (name "Net-(C12-Pad2)") (class "Default")
      (node (ref "C12") (pin "2") (pinfunction "2_2") (pintype "passive"))
      (node (ref "C9") (pin "2") (pinfunction "2_2") (pintype "passive"))
      (node (ref "R14") (pin "1") (pinfunction "1_1") (pintype "passive"))
      (node (ref "R16") (pin "1") (pinfunction "1_1") (pintype "passive"))
    )
    (net (code "30") (name "Net-(CVOUT1-Pad1)") (class "Default")
      (node (ref "CVOUT1") (pin "1") (pinfunction "1_1") (pintype "passive"))
      (node (ref "R22") (pin "2") (pinfunction "2_2") (pintype "passive"))
    )
    (net (code "31") (name "Net-(CVOUT2-Pad1)") (class "Default")
      (node (ref "CVOUT2") (pin "1") (pinfunction "1_1") (pintype "passive"))
      (node (ref "R27") (pin "2") (pinfunction "2_2") (pintype "passive"))
    )
    (net (code "32") (name "Net-(CVOUT3-Pad1)") (class "Default")
      (node (ref "CVOUT3") (pin "1") (pinfunction "1_1") (pintype "passive"))
      (node (ref "R32") (pin "2") (pinfunction "2_2") (pintype "passive"))
    )
    (net (code "33") (name "Net-(CVOUT4-Pad1)") (class "Default")
      (node (ref "CVOUT4") (pin "1") (pinfunction "1_1") (pintype "passive"))
      (node (ref "R38") (pin "2") (pinfunction "2_2") (pintype "passive"))
    )
    (net (code "34") (name "Net-(D1-Pad+)") (class "Default")
      (node (ref "D1") (pin "+") (pinfunction "+_+") (pintype "passive"))
      (node (ref "P4") (pin "10") (pinfunction "+12V_10") (pintype "bidirectional"))
      (node (ref "P4") (pin "9") (pinfunction "+12V_9") (pintype "bidirectional"))
    )
    (net (code "35") (name "Net-(D2-Pad-)") (class "Default")
      (node (ref "D2") (pin "-") (pinfunction "-_-") (pintype "passive"))
      (node (ref "P4") (pin "1") (pinfunction "-12V_1") (pintype "bidirectional"))
      (node (ref "P4") (pin "2") (pinfunction "-12V_2") (pintype "bidirectional"))
    )
    (net (code "36") (name "Net-(F1-P$2)") (class "Default")
      (node (ref "D1") (pin "-") (pinfunction "-_-") (pintype "passive"))
      (node (ref "F1") (pin "2") (pinfunction "P$2_2") (pintype "bidirectional"))
    )
    (net (code "37") (name "Net-(F2-P$2)") (class "Default")
      (node (ref "D2") (pin "+") (pinfunction "+_+") (pintype "passive"))
      (node (ref "F2") (pin "2") (pinfunction "P$2_2") (pintype "bidirectional"))
    )
    (net (code "38") (name "Net-(IC1A--IN)") (class "Default")
      (node (ref "IC1") (pin "2") (pinfunction "-IN_2") (pintype "input"))
      (node (ref "R18") (pin "2") (pinfunction "2_2") (pintype "passive"))
      (node (ref "R19") (pin "1") (pinfunction "1_1") (pintype "passive"))
    )
    (net (code "39") (name "Net-(IC1A-OUT)") (class "Default")
      (node (ref "IC1") (pin "1") (pinfunction "OUT_1") (pintype "output"))
      (node (ref "R19") (pin "2") (pinfunction "2_2") (pintype "passive"))
      (node (ref "R20") (pin "1") (pinfunction "1_1") (pintype "passive"))
    )
    (net (code "40") (name "Net-(IC1B--IN)") (class "Default")
      (node (ref "IC1") (pin "6") (pinfunction "-IN_6") (pintype "input"))
      (node (ref "R20") (pin "2") (pinfunction "2_2") (pintype "passive"))
      (node (ref "R21") (pin "1") (pinfunction "1_1") (pintype "passive"))
    )
    (net (code "41") (name "Net-(IC1B-OUT)") (class "Default")
      (node (ref "IC1") (pin "7") (pinfunction "OUT_7") (pintype "output"))
      (node (ref "R21") (pin "2") (pinfunction "2_2") (pintype "passive"))
      (node (ref "R22") (pin "1") (pinfunction "1_1") (pintype "passive"))
    )
    (net (code "42") (name "Net-(IC1C--IN)") (class "Default")
      (node (ref "IC1") (pin "9") (pinfunction "-IN_9") (pintype "input"))
      (node (ref "R23") (pin "2") (pinfunction "2_2") (pintype "passive"))
      (node (ref "R24") (pin "1") (pinfunction "1_1") (pintype "passive"))
    )
    (net (code "43") (name "Net-(IC1C-OUT)") (class "Default")
      (node (ref "IC1") (pin "8") (pinfunction "OUT_8") (pintype "output"))
      (node (ref "R24") (pin "2") (pinfunction "2_2") (pintype "passive"))
      (node (ref "R25") (pin "1") (pinfunction "1_1") (pintype "passive"))
    )
    (net (code "44") (name "Net-(IC1D--IN)") (class "Default")
      (node (ref "IC1") (pin "13") (pinfunction "-IN_13") (pintype "input"))
      (node (ref "R25") (pin "2") (pinfunction "2_2") (pintype "passive"))
      (node (ref "R26") (pin "1") (pinfunction "1_1") (pintype "passive"))
    )
    (net (code "45") (name "Net-(IC1D-OUT)") (class "Default")
      (node (ref "IC1") (pin "14") (pinfunction "OUT_14") (pintype "output"))
      (node (ref "R26") (pin "2") (pinfunction "2_2") (pintype "passive"))
      (node (ref "R27") (pin "1") (pinfunction "1_1") (pintype "passive"))
    )
    (net (code "46") (name "Net-(IC2A-P$2)") (class "Default")
      (node (ref "IC2") (pin "2") (pinfunction "P$2_2") (pintype "bidirectional"))
      (node (ref "R4") (pin "1") (pinfunction "1_1") (pintype "passive"))
      (node (ref "R8") (pin "2") (pinfunction "2_2") (pintype "passive"))
    )
    (net (code "47") (name "Net-(IC2A-P$3)") (class "Default")
      (node (ref "IC2") (pin "1") (pinfunction "P$3_1") (pintype "bidirectional"))
      (node (ref "R14") (pin "2") (pinfunction "2_2") (pintype "passive"))
      (node (ref "R8") (pin "1") (pinfunction "1_1") (pintype "passive"))
    )
    (net (code "48") (name "Net-(IC2B-P$2)") (class "Default")
      (node (ref "IC2") (pin "6") (pinfunction "P$2_6") (pintype "bidirectional"))
      (node (ref "R5") (pin "1") (pinfunction "1_1") (pintype "passive"))
      (node (ref "R9") (pin "2") (pinfunction "2_2") (pintype "passive"))
    )
    (net (code "49") (name "Net-(IC2B-P$3)") (class "Default")
      (node (ref "IC2") (pin "7") (pinfunction "P$3_7") (pintype "bidirectional"))
      (node (ref "R15") (pin "2") (pinfunction "2_2") (pintype "passive"))
      (node (ref "R9") (pin "1") (pinfunction "1_1") (pintype "passive"))
    )
    (net (code "50") (name "Net-(IC3A-P$2)") (class "Default")
      (node (ref "C7") (pin "2") (pinfunction "2_2") (pintype "passive"))
      (node (ref "IC3") (pin "2") (pinfunction "P$2_2") (pintype "bidirectional"))
      (node (ref "R10") (pin "1") (pinfunction "1_1") (pintype "passive"))
      (node (ref "R6") (pin "2") (pinfunction "2_2") (pintype "passive"))
    )
    (net (code "51") (name "Net-(IC3A-P$3)") (class "Default")
      (node (ref "C7") (pin "1") (pinfunction "1_1") (pintype "passive"))
      (node (ref "IC3") (pin "1") (pinfunction "P$3_1") (pintype "bidirectional"))
      (node (ref "R10") (pin "2") (pinfunction "2_2") (pintype "passive"))
      (node (ref "R12") (pin "1") (pinfunction "1_1") (pintype "passive"))
    )
    (net (code "52") (name "Net-(IC3B-P$2)") (class "Default")
      (node (ref "C8") (pin "2") (pinfunction "2_2") (pintype "passive"))
      (node (ref "IC3") (pin "6") (pinfunction "P$2_6") (pintype "bidirectional"))
      (node (ref "R11") (pin "1") (pinfunction "1_1") (pintype "passive"))
      (node (ref "R7") (pin "2") (pinfunction "2_2") (pintype "passive"))
    )
    (net (code "53") (name "Net-(IC3B-P$3)") (class "Default")
      (node (ref "C8") (pin "1") (pinfunction "1_1") (pintype "passive"))
      (node (ref "IC3") (pin "7") (pinfunction "P$3_7") (pintype "bidirectional"))
      (node (ref "R11") (pin "2") (pinfunction "2_2") (pintype "passive"))
      (node (ref "R13") (pin "1") (pinfunction "1_1") (pintype "passive"))
    )
    (net (code "54") (name "Net-(IC4-VMID)") (class "Default")
      (node (ref "C11") (pin "1") (pinfunction "1_1") (pintype "passive"))
      (node (ref "C14") (pin "1") (pinfunction "1_1") (pintype "passive"))
      (node (ref "IC4") (pin "16") (pinfunction "VMID_16") (pintype "bidirectional"))
    )
    (net (code "55") (name "Net-(IC4-XTI{slash}MCLK)") (class "Default")
      (node (ref "C4") (pin "2") (pinfunction "2_2") (pintype "passive"))
      (node (ref "IC4") (pin "25") (pinfunction "XTI/MCLK_25") (pintype "bidirectional"))
      (node (ref "Q1") (pin "1") (pinfunction "1_1") (pintype "passive"))
    )
    (net (code "56") (name "Net-(IC4-XTO)") (class "Default")
      (node (ref "C5") (pin "2") (pinfunction "2_2") (pintype "passive"))
      (node (ref "IC4") (pin "26") (pinfunction "XTO_26") (pintype "bidirectional"))
      (node (ref "Q1") (pin "2") (pinfunction "2_2") (pintype "passive"))
    )
    (net (code "57") (name "Net-(IC5A--IN)") (class "Default")
      (node (ref "IC5") (pin "2") (pinfunction "-IN_2") (pintype "input"))
      (node (ref "R28") (pin "2") (pinfunction "2_2") (pintype "passive"))
      (node (ref "R29") (pin "1") (pinfunction "1_1") (pintype "passive"))
    )
    (net (code "58") (name "Net-(IC5A-OUT)") (class "Default")
      (node (ref "IC5") (pin "1") (pinfunction "OUT_1") (pintype "output"))
      (node (ref "R29") (pin "2") (pinfunction "2_2") (pintype "passive"))
      (node (ref "R30") (pin "1") (pinfunction "1_1") (pintype "passive"))
    )
    (net (code "59") (name "Net-(IC5B--IN)") (class "Default")
      (node (ref "IC5") (pin "6") (pinfunction "-IN_6") (pintype "input"))
      (node (ref "R30") (pin "2") (pinfunction "2_2") (pintype "passive"))
      (node (ref "R31") (pin "1") (pinfunction "1_1") (pintype "passive"))
    )
    (net (code "60") (name "Net-(IC5B-OUT)") (class "Default")
      (node (ref "IC5") (pin "7") (pinfunction "OUT_7") (pintype "output"))
      (node (ref "R31") (pin "2") (pinfunction "2_2") (pintype "passive"))
      (node (ref "R32") (pin "1") (pinfunction "1_1") (pintype "passive"))
    )
    (net (code "61") (name "Net-(IC5C--IN)") (class "Default")
      (node (ref "IC5") (pin "9") (pinfunction "-IN_9") (pintype "input"))
      (node (ref "R34") (pin "2") (pinfunction "2_2") (pintype "passive"))
      (node (ref "R35") (pin "1") (pinfunction "1_1") (pintype "passive"))
    )
    (net (code "62") (name "Net-(IC5C-OUT)") (class "Default")
      (node (ref "IC5") (pin "8") (pinfunction "OUT_8") (pintype "output"))
      (node (ref "R35") (pin "2") (pinfunction "2_2") (pintype "passive"))
      (node (ref "R36") (pin "1") (pinfunction "1_1") (pintype "passive"))
    )
    (net (code "63") (name "Net-(IC5D--IN)") (class "Default")
      (node (ref "IC5") (pin "13") (pinfunction "-IN_13") (pintype "input"))
      (node (ref "R36") (pin "2") (pinfunction "2_2") (pintype "passive"))
      (node (ref "R37") (pin "1") (pinfunction "1_1") (pintype "passive"))
    )
    (net (code "64") (name "Net-(IC5D-OUT)") (class "Default")
      (node (ref "IC5") (pin "14") (pinfunction "OUT_14") (pintype "output"))
      (node (ref "R37") (pin "2") (pinfunction "2_2") (pintype "passive"))
      (node (ref "R38") (pin "1") (pinfunction "1_1") (pintype "passive"))
    )
    (net (code "65") (name "Net-(IC10A-P$2)") (class "Default")
      (node (ref "C49") (pin "1") (pinfunction "1_1") (pintype "passive"))
      (node (ref "CVIN(100K)0") (pin "1") (pinfunction "1_1") (pintype "passive"))
      (node (ref "IC10") (pin "2") (pinfunction "P$2_2") (pintype "bidirectional"))
      (node (ref "R3") (pin "1") (pinfunction "1_1") (pintype "passive"))
      (node (ref "R46") (pin "1") (pinfunction "1_1") (pintype "passive"))
    )
    (net (code "66") (name "Net-(IC10B-P$2)") (class "Default")
      (node (ref "C50") (pin "1") (pinfunction "1_1") (pintype "passive"))
      (node (ref "CVIN(100K)1") (pin "1") (pinfunction "1_1") (pintype "passive"))
      (node (ref "IC10") (pin "6") (pinfunction "P$2_6") (pintype "bidirectional"))
      (node (ref "R39") (pin "1") (pinfunction "1_1") (pintype "passive"))
      (node (ref "R47") (pin "1") (pinfunction "1_1") (pintype "passive"))
    )
    (net (code "67") (name "Net-(IC10C-P$2)") (class "Default")
      (node (ref "C53") (pin "1") (pinfunction "1_1") (pintype "passive"))
      (node (ref "CVIN(100K)2") (pin "1") (pinfunction "1_1") (pintype "passive"))
      (node (ref "IC10") (pin "9") (pinfunction "P$2_9") (pintype "bidirectional"))
      (node (ref "R40") (pin "1") (pinfunction "1_1") (pintype "passive"))
      (node (ref "R58") (pin "1") (pinfunction "1_1") (pintype "passive"))
    )
    (net (code "68") (name "Net-(IC10D-P$2)") (class "Default")
      (node (ref "C54") (pin "1") (pinfunction "1_1") (pintype "passive"))
      (node (ref "CVIN(100K)3") (pin "1") (pinfunction "1_1") (pintype "passive"))
      (node (ref "IC10") (pin "13") (pinfunction "P$2_13") (pintype "bidirectional"))
      (node (ref "R41") (pin "1") (pinfunction "1_1") (pintype "passive"))
      (node (ref "R59") (pin "1") (pinfunction "1_1") (pintype "passive"))
    )
    (net (code "69") (name "Net-(J_LIN-Pad1)") (class "Default")
      (node (ref "J_LIN") (pin "1") (pinfunction "1_1") (pintype "passive"))
      (node (ref "R5") (pin "2") (pinfunction "2_2") (pintype "passive"))
    )
    (net (code "70") (name "Net-(J_LOUT-Pad1)") (class "Default")
      (node (ref "J_LOUT") (pin "1") (pinfunction "1_1") (pintype "passive"))
      (node (ref "R13") (pin "2") (pinfunction "2_2") (pintype "passive"))
    )
    (net (code "71") (name "Net-(J_RIN-Pad1)") (class "Default")
      (node (ref "J_RIN") (pin "1") (pinfunction "1_1") (pintype "passive"))
      (node (ref "R4") (pin "2") (pinfunction "2_2") (pintype "passive"))
    )
    (net (code "72") (name "Net-(J_ROUT-Pad1)") (class "Default")
      (node (ref "J_ROUT") (pin "1") (pinfunction "1_1") (pintype "passive"))
      (node (ref "R12") (pin "2") (pinfunction "2_2") (pintype "passive"))
    )
    (net (code "73") (name "Net-(U$1-VOUTA)") (class "Default")
      (node (ref "R18") (pin "1") (pinfunction "1_1") (pintype "passive"))
      (node (ref "U$1") (pin "8") (pinfunction "VOUTA_8") (pintype "output"))
    )
    (net (code "74") (name "Net-(U$1-VOUTB)") (class "Default")
      (node (ref "R23") (pin "1") (pinfunction "1_1") (pintype "passive"))
      (node (ref "U$1") (pin "6") (pinfunction "VOUTB_6") (pintype "output"))
    )
    (net (code "75") (name "Net-(U$2-VOUTA)") (class "Default")
      (node (ref "R28") (pin "1") (pinfunction "1_1") (pintype "passive"))
      (node (ref "U$2") (pin "8") (pinfunction "VOUTA_8") (pintype "output"))
    )
    (net (code "76") (name "Net-(U$2-VOUTB)") (class "Default")
      (node (ref "R34") (pin "1") (pinfunction "1_1") (pintype "passive"))
      (node (ref "U$2") (pin "6") (pinfunction "VOUTB_6") (pintype "output"))
    )
    (net (code "77") (name "RIN") (class "Default")
      (node (ref "C12") (pin "1") (pinfunction "1_1") (pintype "passive"))
      (node (ref "IC4") (pin "19") (pinfunction "RLINEIN_19") (pintype "bidirectional"))
    )
    (net (code "78") (name "ROUT") (class "Default")
      (node (ref "C2") (pin "2") (pinfunction "2_2") (pintype "passive"))
      (node (ref "IC4") (pin "13") (pinfunction "ROUT_13") (pintype "bidirectional"))
    )
    (net (code "79") (name "SPI_CLK") (class "Default")
      (node (ref "MS2") (pin "11") (pinfunction "SCK_11") (pintype "bidirectional"))
      (node (ref "U$1") (pin "3") (pinfunction "SCK_3") (pintype "input"))
      (node (ref "U$2") (pin "3") (pinfunction "SCK_3") (pintype "input"))
      (node (ref "U2") (pin "11") (pinfunction "CLK_11") (pintype "input"))
    )
    (net (code "80") (name "SPI_MISO") (class "Default")
      (node (ref "MS2") (pin "13") (pinfunction "MISO_13") (pintype "bidirectional"))
      (node (ref "U2") (pin "10") (pinfunction "DOUT_10") (pintype "output"))
    )
    (net (code "81") (name "SPI_MOSI") (class "Default")
      (node (ref "MS2") (pin "12") (pinfunction "MOSI_12") (pintype "bidirectional"))
      (node (ref "U$1") (pin "4") (pinfunction "SDI_4") (pintype "input"))
      (node (ref "U$2") (pin "4") (pinfunction "SDI_4") (pintype "input"))
      (node (ref "U2") (pin "9") (pinfunction "DIN_9") (pintype "input"))
    )
    (net (code "82") (name "unconnected-(IC4-CLKOUT-Pad2)") (class "Default")
      (node (ref "IC4") (pin "2") (pinfunction "CLKOUT_2") (pintype "bidirectional"))
    )
    (net (code "83") (name "unconnected-(IC4-LHPOUT-Pad9)") (class "Default")
      (node (ref "IC4") (pin "9") (pinfunction "LHPOUT_9") (pintype "bidirectional"))
    )
    (net (code "84") (name "unconnected-(IC4-MICBIAS-Pad17)") (class "Default")
      (node (ref "IC4") (pin "17") (pinfunction "MICBIAS_17") (pintype "bidirectional"))
    )
    (net (code "85") (name "unconnected-(IC4-MICIN-Pad18)") (class "Default")
      (node (ref "IC4") (pin "18") (pinfunction "MICIN_18") (pintype "bidirectional"))
    )
    (net (code "86") (name "unconnected-(IC4-RHPOUT-Pad10)") (class "Default")
      (node (ref "IC4") (pin "10") (pinfunction "RHPOUT_10") (pintype "bidirectional"))
    )
    (net (code "87") (name "unconnected-(MS2-A2{slash}I34-Pad7)") (class "Default")
      (node (ref "MS2") (pin "7") (pinfunction "A2/I34_7") (pintype "bidirectional"))
    )
    (net (code "88") (name "unconnected-(MS2-A3{slash}I39-Pad8)") (class "Default")
      (node (ref "MS2") (pin "8") (pinfunction "A3/I39_8") (pintype "bidirectional"))
    )
    (net (code "89") (name "unconnected-(MS2-A4{slash}I36-Pad9)") (class "Default")
      (node (ref "MS2") (pin "9") (pinfunction "A4/I36_9") (pintype "bidirectional"))
    )
    (net (code "90") (name "unconnected-(MS2-EN-Pad27)") (class "Default")
      (node (ref "MS2") (pin "27") (pinfunction "EN_27") (pintype "passive"))
    )
    (net (code "91") (name "unconnected-(MS2-IO13-Pad25)") (class "Default")
      (node (ref "MS2") (pin "25") (pinfunction "IO13_25") (pintype "bidirectional"))
    )
    (net (code "92") (name "unconnected-(MS2-NC-Pad3)") (class "Default")
      (node (ref "MS2") (pin "3") (pinfunction "NC_3") (pintype "passive"))
    )
    (net (code "93") (name "unconnected-(MS2-RX{slash}IO16-Pad14)") (class "Default")
      (node (ref "MS2") (pin "14") (pinfunction "RX/IO16_14") (pintype "bidirectional"))
    )
    (net (code "94") (name "unconnected-(MS2-SCL-Pad18)") (class "Default")
      (node (ref "MS2") (pin "18") (pinfunction "SCL_18") (pintype "bidirectional"))
    )
    (net (code "95") (name "unconnected-(MS2-SDA-Pad17)") (class "Default")
      (node (ref "MS2") (pin "17") (pinfunction "SDA_17") (pintype "bidirectional"))
    )
    (net (code "96") (name "unconnected-(MS2-TX{slash}IO17-Pad15)") (class "Default")
      (node (ref "MS2") (pin "15") (pinfunction "TX/IO17_15") (pintype "bidirectional"))
    )
    (net (code "97") (name "unconnected-(MS2-~{RESET}-Pad1)") (class "Default")
      (node (ref "MS2") (pin "1") (pinfunction "~{RESET}_1") (pintype "input"))
    )
    (net (code "98") (name "unconnected-(U2-NC-Pad6)") (class "Default")
      (node (ref "U2") (pin "6") (pinfunction "NC_6") (pintype "no_connect"))
    )
    (net (code "99") (name "unconnected-(U2-NC_2-Pad5)") (class "Default")
      (node (ref "U2") (pin "5") (pinfunction "NC_2_5") (pintype "no_connect"))
    )
  )
)
